# Headstage_Mainboard.net
KiCad netlist of a schematic drawn in Altium Designer
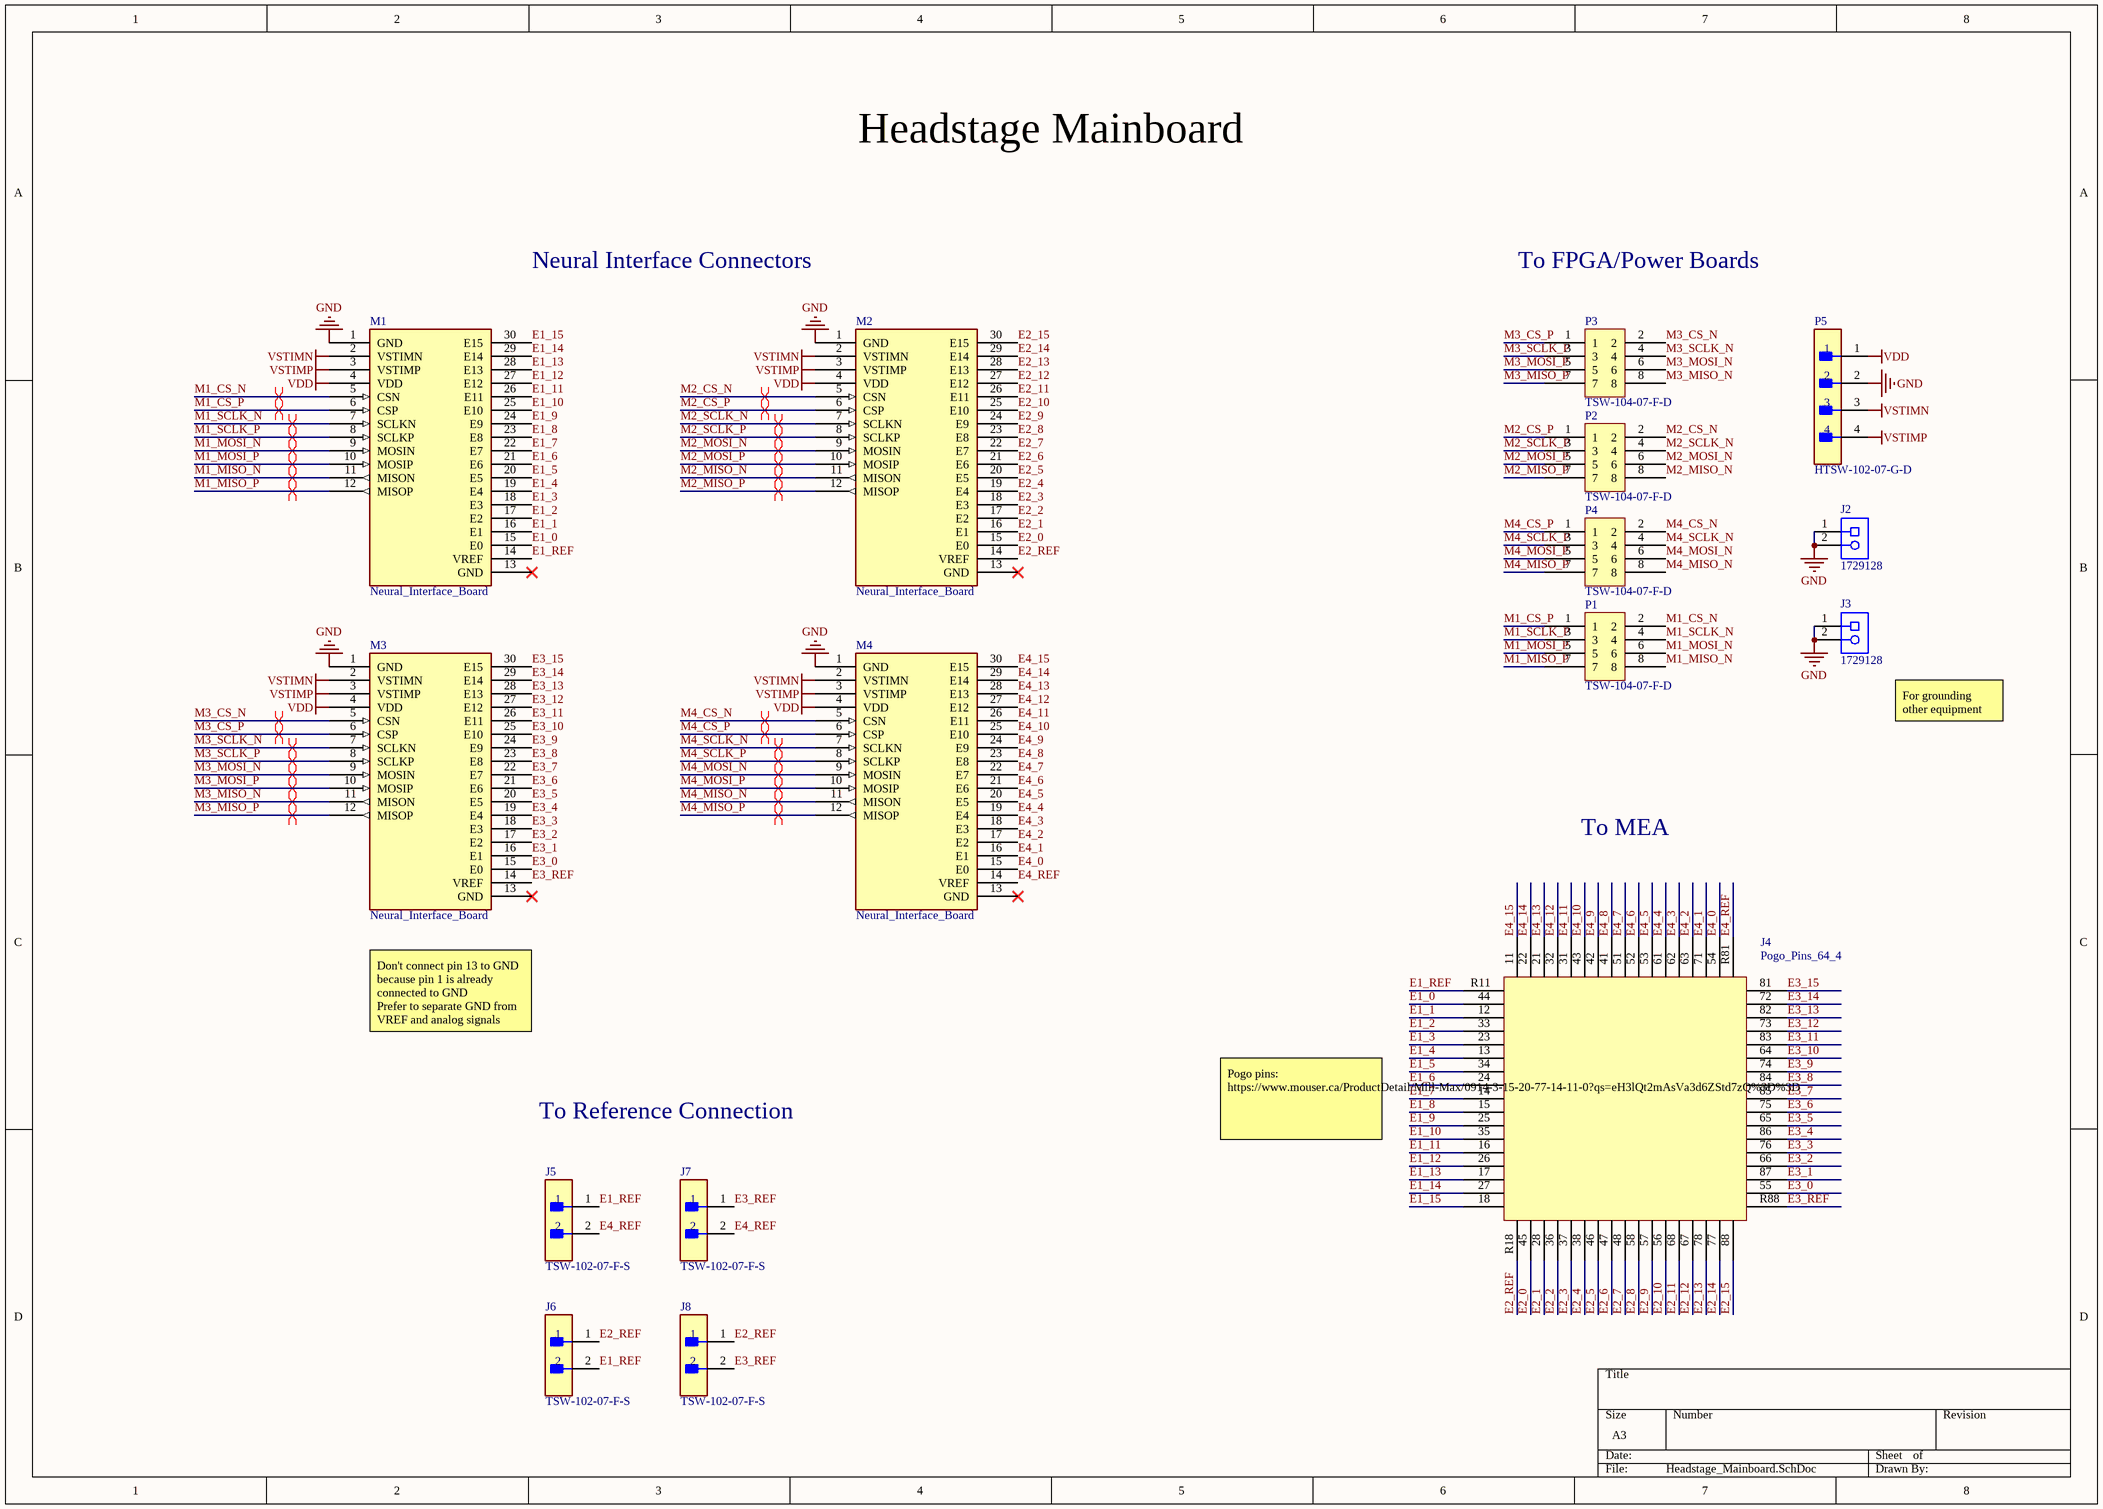
[diagram p0: Headstage_Mainboard.SchDoc]

(export (version "E")
  (design (tool "Eeschema 10.0.6"))
  (components
    (comp (ref "J2")
      (value "1729128")
      (footprint "PHOE-1729128-2_V")
      (description "PCB Terminal Block, 13.5 A, 400 V, 2-Pin THD, RoHS, Bulk")
      (fields (field (name "MANUFACTURER") "Phoenix Contact"))
      (libsource (lib "Altium Content Vault") (part "CN-2P-F-R2"))
    )
    (comp (ref "J3")
      (value "1729128")
      (footprint "PHOE-1729128-2_V")
      (description "PCB Terminal Block, 13.5 A, 400 V, 2-Pin THD, RoHS, Bulk")
      (fields (field (name "MANUFACTURER") "Phoenix Contact"))
      (libsource (lib "Altium Content Vault") (part "CN-2P-F-R2"))
    )
    (comp (ref "J4")
      (value "Pogo_Pins_64_4")
      (footprint "Pogo_Pins_64_4")
      (description "Pogo pins, 64 recording electrodes, 4 reference electrodes")
      (libsource (lib "OpenMEA") (part "Pogo_Pins_64_4"))
    )
    (comp (ref "J5")
      (value "TSW-102-07-F-S")
      (footprint "FP-TSW-102-07-F-S-MFG")
      (description "CONN HEADER VERT 2POS 2.54MM")
      (libsource (lib "Altium Content Vault") (part "3bc925449376181038e59eaffc5286c"))
    )
    (comp (ref "J6")
      (value "TSW-102-07-F-S")
      (footprint "FP-TSW-102-07-F-S-MFG")
      (description "CONN HEADER VERT 2POS 2.54MM")
      (libsource (lib "Altium Content Vault") (part "3bc925449376181038e59eaffc5286c"))
    )
    (comp (ref "J7")
      (value "TSW-102-07-F-S")
      (footprint "FP-TSW-102-07-F-S-MFG")
      (description "CONN HEADER VERT 2POS 2.54MM")
      (libsource (lib "Altium Content Vault") (part "3bc925449376181038e59eaffc5286c"))
    )
    (comp (ref "J8")
      (value "TSW-102-07-F-S")
      (footprint "FP-TSW-102-07-F-S-MFG")
      (description "CONN HEADER VERT 2POS 2.54MM")
      (libsource (lib "Altium Content Vault") (part "3bc925449376181038e59eaffc5286c"))
    )
    (comp (ref "M1")
      (value "Neural_Interface_Board")
      (footprint "Neural_Interface_Board")
      (libsource (lib "OpenMEA") (part "Neural_Interface_Board"))
    )
    (comp (ref "M2")
      (value "Neural_Interface_Board")
      (footprint "Neural_Interface_Board")
      (libsource (lib "OpenMEA") (part "Neural_Interface_Board"))
    )
    (comp (ref "M3")
      (value "Neural_Interface_Board")
      (footprint "Neural_Interface_Board")
      (libsource (lib "OpenMEA") (part "Neural_Interface_Board"))
    )
    (comp (ref "M4")
      (value "Neural_Interface_Board")
      (footprint "Neural_Interface_Board")
      (libsource (lib "OpenMEA") (part "Neural_Interface_Board"))
    )
    (comp (ref "P1")
      (value "TSW-104-07-F-D")
      (footprint "SAMTEC_TSW-104-07-F-D")
      (fields (field (name "MANUFACTURER") "Samtec"))
      (libsource (lib "LVDS") (part "TSW-104-07-F-D"))
    )
    (comp (ref "P2")
      (value "TSW-104-07-F-D")
      (footprint "SAMTEC_TSW-104-07-F-D")
      (fields (field (name "MANUFACTURER") "Samtec"))
      (libsource (lib "LVDS") (part "TSW-104-07-F-D"))
    )
    (comp (ref "P3")
      (value "TSW-104-07-F-D")
      (footprint "SAMTEC_TSW-104-07-F-D")
      (fields (field (name "MANUFACTURER") "Samtec"))
      (libsource (lib "LVDS") (part "TSW-104-07-F-D"))
    )
    (comp (ref "P4")
      (value "TSW-104-07-F-D")
      (footprint "SAMTEC_TSW-104-07-F-D")
      (fields (field (name "MANUFACTURER") "Samtec"))
      (libsource (lib "LVDS") (part "TSW-104-07-F-D"))
    )
    (comp (ref "P5")
      (value "HTSW-102-07-G-D")
      (footprint "FP-HTSW-102-07-G-D-MFG")
      (description "CONN HEADER VERT 4POS 2.54MM")
      (fields
        (field (name "MANUFACTURER") "Samtec")
        (field (name "OCTOPART") "https://octopart.com/htsw-102-07-g-d-samtec-10531767")
      )
      (libsource (lib "Altium Content Vault") (part "299a8cea1bdcbc3624fe62c390fa72c"))
    )
  )
  (nets
    (net (code "1") (name "/E1_0") (class "Default")
      (node (ref "J4") (pin "44") (pintype "passive"))
      (node (ref "M1") (pin "15") (pinfunction "E0_15") (pintype "passive"))
    )
    (net (code "2") (name "/E1_1") (class "Default")
      (node (ref "J4") (pin "12") (pintype "passive"))
      (node (ref "M1") (pin "16") (pinfunction "E1_16") (pintype "passive"))
    )
    (net (code "3") (name "/E1_2") (class "Default")
      (node (ref "J4") (pin "33") (pintype "passive"))
      (node (ref "M1") (pin "17") (pinfunction "E2_17") (pintype "passive"))
    )
    (net (code "4") (name "/E1_3") (class "Default")
      (node (ref "J4") (pin "23") (pintype "passive"))
      (node (ref "M1") (pin "18") (pinfunction "E3_18") (pintype "passive"))
    )
    (net (code "5") (name "/E1_4") (class "Default")
      (node (ref "J4") (pin "13") (pintype "passive"))
      (node (ref "M1") (pin "19") (pinfunction "E4_19") (pintype "passive"))
    )
    (net (code "6") (name "/E1_5") (class "Default")
      (node (ref "J4") (pin "34") (pintype "passive"))
      (node (ref "M1") (pin "20") (pinfunction "E5_20") (pintype "passive"))
    )
    (net (code "7") (name "/E1_6") (class "Default")
      (node (ref "J4") (pin "24") (pintype "passive"))
      (node (ref "M1") (pin "21") (pinfunction "E6_21") (pintype "passive"))
    )
    (net (code "8") (name "/E1_7") (class "Default")
      (node (ref "J4") (pin "14") (pintype "passive"))
      (node (ref "M1") (pin "22") (pinfunction "E7_22") (pintype "passive"))
    )
    (net (code "9") (name "/E1_8") (class "Default")
      (node (ref "J4") (pin "15") (pintype "passive"))
      (node (ref "M1") (pin "23") (pinfunction "E8_23") (pintype "passive"))
    )
    (net (code "10") (name "/E1_9") (class "Default")
      (node (ref "J4") (pin "25") (pintype "passive"))
      (node (ref "M1") (pin "24") (pinfunction "E9_24") (pintype "passive"))
    )
    (net (code "11") (name "/E1_10") (class "Default")
      (node (ref "J4") (pin "35") (pintype "passive"))
      (node (ref "M1") (pin "25") (pinfunction "E10_25") (pintype "passive"))
    )
    (net (code "12") (name "/E1_11") (class "Default")
      (node (ref "J4") (pin "16") (pintype "passive"))
      (node (ref "M1") (pin "26") (pinfunction "E11_26") (pintype "passive"))
    )
    (net (code "13") (name "/E1_12") (class "Default")
      (node (ref "J4") (pin "26") (pintype "passive"))
      (node (ref "M1") (pin "27") (pinfunction "E12_27") (pintype "passive"))
    )
    (net (code "14") (name "/E1_13") (class "Default")
      (node (ref "J4") (pin "17") (pintype "passive"))
      (node (ref "M1") (pin "28") (pinfunction "E13_28") (pintype "passive"))
    )
    (net (code "15") (name "/E1_14") (class "Default")
      (node (ref "J4") (pin "27") (pintype "passive"))
      (node (ref "M1") (pin "29") (pinfunction "E14_29") (pintype "passive"))
    )
    (net (code "16") (name "/E1_15") (class "Default")
      (node (ref "J4") (pin "18") (pintype "passive"))
      (node (ref "M1") (pin "30") (pinfunction "E15_30") (pintype "passive"))
    )
    (net (code "17") (name "/E1_REF") (class "Default")
      (node (ref "J4") (pin "R11") (pintype "passive"))
      (node (ref "J5") (pin "1") (pinfunction "1_1") (pintype "passive"))
      (node (ref "J6") (pin "2") (pinfunction "2_2") (pintype "passive"))
      (node (ref "M1") (pin "14") (pinfunction "VREF_14") (pintype "passive"))
    )
    (net (code "18") (name "/E2_0") (class "Default")
      (node (ref "J4") (pin "45") (pintype "passive"))
      (node (ref "M2") (pin "15") (pinfunction "E0_15") (pintype "passive"))
    )
    (net (code "19") (name "/E2_1") (class "Default")
      (node (ref "J4") (pin "28") (pintype "passive"))
      (node (ref "M2") (pin "16") (pinfunction "E1_16") (pintype "passive"))
    )
    (net (code "20") (name "/E2_2") (class "Default")
      (node (ref "J4") (pin "36") (pintype "passive"))
      (node (ref "M2") (pin "17") (pinfunction "E2_17") (pintype "passive"))
    )
    (net (code "21") (name "/E2_3") (class "Default")
      (node (ref "J4") (pin "37") (pintype "passive"))
      (node (ref "M2") (pin "18") (pinfunction "E3_18") (pintype "passive"))
    )
    (net (code "22") (name "/E2_4") (class "Default")
      (node (ref "J4") (pin "38") (pintype "passive"))
      (node (ref "M2") (pin "19") (pinfunction "E4_19") (pintype "passive"))
    )
    (net (code "23") (name "/E2_5") (class "Default")
      (node (ref "J4") (pin "46") (pintype "passive"))
      (node (ref "M2") (pin "20") (pinfunction "E5_20") (pintype "passive"))
    )
    (net (code "24") (name "/E2_6") (class "Default")
      (node (ref "J4") (pin "47") (pintype "passive"))
      (node (ref "M2") (pin "21") (pinfunction "E6_21") (pintype "passive"))
    )
    (net (code "25") (name "/E2_7") (class "Default")
      (node (ref "J4") (pin "48") (pintype "passive"))
      (node (ref "M2") (pin "22") (pinfunction "E7_22") (pintype "passive"))
    )
    (net (code "26") (name "/E2_8") (class "Default")
      (node (ref "J4") (pin "58") (pintype "passive"))
      (node (ref "M2") (pin "23") (pinfunction "E8_23") (pintype "passive"))
    )
    (net (code "27") (name "/E2_9") (class "Default")
      (node (ref "J4") (pin "57") (pintype "passive"))
      (node (ref "M2") (pin "24") (pinfunction "E9_24") (pintype "passive"))
    )
    (net (code "28") (name "/E2_10") (class "Default")
      (node (ref "J4") (pin "56") (pintype "passive"))
      (node (ref "M2") (pin "25") (pinfunction "E10_25") (pintype "passive"))
    )
    (net (code "29") (name "/E2_11") (class "Default")
      (node (ref "J4") (pin "68") (pintype "passive"))
      (node (ref "M2") (pin "26") (pinfunction "E11_26") (pintype "passive"))
    )
    (net (code "30") (name "/E2_12") (class "Default")
      (node (ref "J4") (pin "67") (pintype "passive"))
      (node (ref "M2") (pin "27") (pinfunction "E12_27") (pintype "passive"))
    )
    (net (code "31") (name "/E2_13") (class "Default")
      (node (ref "J4") (pin "78") (pintype "passive"))
      (node (ref "M2") (pin "28") (pinfunction "E13_28") (pintype "passive"))
    )
    (net (code "32") (name "/E2_14") (class "Default")
      (node (ref "J4") (pin "77") (pintype "passive"))
      (node (ref "M2") (pin "29") (pinfunction "E14_29") (pintype "passive"))
    )
    (net (code "33") (name "/E2_15") (class "Default")
      (node (ref "J4") (pin "88") (pintype "passive"))
      (node (ref "M2") (pin "30") (pinfunction "E15_30") (pintype "passive"))
    )
    (net (code "34") (name "/E2_REF") (class "Default")
      (node (ref "J4") (pin "R18") (pintype "passive"))
      (node (ref "J6") (pin "1") (pinfunction "1_1") (pintype "passive"))
      (node (ref "J8") (pin "1") (pinfunction "1_1") (pintype "passive"))
      (node (ref "M2") (pin "14") (pinfunction "VREF_14") (pintype "passive"))
    )
    (net (code "35") (name "/E3_0") (class "Default")
      (node (ref "J4") (pin "55") (pintype "passive"))
      (node (ref "M3") (pin "15") (pinfunction "E0_15") (pintype "passive"))
    )
    (net (code "36") (name "/E3_1") (class "Default")
      (node (ref "J4") (pin "87") (pintype "passive"))
      (node (ref "M3") (pin "16") (pinfunction "E1_16") (pintype "passive"))
    )
    (net (code "37") (name "/E3_2") (class "Default")
      (node (ref "J4") (pin "66") (pintype "passive"))
      (node (ref "M3") (pin "17") (pinfunction "E2_17") (pintype "passive"))
    )
    (net (code "38") (name "/E3_3") (class "Default")
      (node (ref "J4") (pin "76") (pintype "passive"))
      (node (ref "M3") (pin "18") (pinfunction "E3_18") (pintype "passive"))
    )
    (net (code "39") (name "/E3_4") (class "Default")
      (node (ref "J4") (pin "86") (pintype "passive"))
      (node (ref "M3") (pin "19") (pinfunction "E4_19") (pintype "passive"))
    )
    (net (code "40") (name "/E3_5") (class "Default")
      (node (ref "J4") (pin "65") (pintype "passive"))
      (node (ref "M3") (pin "20") (pinfunction "E5_20") (pintype "passive"))
    )
    (net (code "41") (name "/E3_6") (class "Default")
      (node (ref "J4") (pin "75") (pintype "passive"))
      (node (ref "M3") (pin "21") (pinfunction "E6_21") (pintype "passive"))
    )
    (net (code "42") (name "/E3_7") (class "Default")
      (node (ref "J4") (pin "85") (pintype "passive"))
      (node (ref "M3") (pin "22") (pinfunction "E7_22") (pintype "passive"))
    )
    (net (code "43") (name "/E3_8") (class "Default")
      (node (ref "J4") (pin "84") (pintype "passive"))
      (node (ref "M3") (pin "23") (pinfunction "E8_23") (pintype "passive"))
    )
    (net (code "44") (name "/E3_9") (class "Default")
      (node (ref "J4") (pin "74") (pintype "passive"))
      (node (ref "M3") (pin "24") (pinfunction "E9_24") (pintype "passive"))
    )
    (net (code "45") (name "/E3_10") (class "Default")
      (node (ref "J4") (pin "64") (pintype "passive"))
      (node (ref "M3") (pin "25") (pinfunction "E10_25") (pintype "passive"))
    )
    (net (code "46") (name "/E3_11") (class "Default")
      (node (ref "J4") (pin "83") (pintype "passive"))
      (node (ref "M3") (pin "26") (pinfunction "E11_26") (pintype "passive"))
    )
    (net (code "47") (name "/E3_12") (class "Default")
      (node (ref "J4") (pin "73") (pintype "passive"))
      (node (ref "M3") (pin "27") (pinfunction "E12_27") (pintype "passive"))
    )
    (net (code "48") (name "/E3_13") (class "Default")
      (node (ref "J4") (pin "82") (pintype "passive"))
      (node (ref "M3") (pin "28") (pinfunction "E13_28") (pintype "passive"))
    )
    (net (code "49") (name "/E3_14") (class "Default")
      (node (ref "J4") (pin "72") (pintype "passive"))
      (node (ref "M3") (pin "29") (pinfunction "E14_29") (pintype "passive"))
    )
    (net (code "50") (name "/E3_15") (class "Default")
      (node (ref "J4") (pin "81") (pintype "passive"))
      (node (ref "M3") (pin "30") (pinfunction "E15_30") (pintype "passive"))
    )
    (net (code "51") (name "/E3_REF") (class "Default")
      (node (ref "J4") (pin "R88") (pintype "passive"))
      (node (ref "J7") (pin "1") (pinfunction "1_1") (pintype "passive"))
      (node (ref "J8") (pin "2") (pinfunction "2_2") (pintype "passive"))
      (node (ref "M3") (pin "14") (pinfunction "VREF_14") (pintype "passive"))
    )
    (net (code "52") (name "/E4_0") (class "Default")
      (node (ref "J4") (pin "54") (pintype "passive"))
      (node (ref "M4") (pin "15") (pinfunction "E0_15") (pintype "passive"))
    )
    (net (code "53") (name "/E4_1") (class "Default")
      (node (ref "J4") (pin "71") (pintype "passive"))
      (node (ref "M4") (pin "16") (pinfunction "E1_16") (pintype "passive"))
    )
    (net (code "54") (name "/E4_2") (class "Default")
      (node (ref "J4") (pin "63") (pintype "passive"))
      (node (ref "M4") (pin "17") (pinfunction "E2_17") (pintype "passive"))
    )
    (net (code "55") (name "/E4_3") (class "Default")
      (node (ref "J4") (pin "62") (pintype "passive"))
      (node (ref "M4") (pin "18") (pinfunction "E3_18") (pintype "passive"))
    )
    (net (code "56") (name "/E4_4") (class "Default")
      (node (ref "J4") (pin "61") (pintype "passive"))
      (node (ref "M4") (pin "19") (pinfunction "E4_19") (pintype "passive"))
    )
    (net (code "57") (name "/E4_5") (class "Default")
      (node (ref "J4") (pin "53") (pintype "passive"))
      (node (ref "M4") (pin "20") (pinfunction "E5_20") (pintype "passive"))
    )
    (net (code "58") (name "/E4_6") (class "Default")
      (node (ref "J4") (pin "52") (pintype "passive"))
      (node (ref "M4") (pin "21") (pinfunction "E6_21") (pintype "passive"))
    )
    (net (code "59") (name "/E4_7") (class "Default")
      (node (ref "J4") (pin "51") (pintype "passive"))
      (node (ref "M4") (pin "22") (pinfunction "E7_22") (pintype "passive"))
    )
    (net (code "60") (name "/E4_8") (class "Default")
      (node (ref "J4") (pin "41") (pintype "passive"))
      (node (ref "M4") (pin "23") (pinfunction "E8_23") (pintype "passive"))
    )
    (net (code "61") (name "/E4_9") (class "Default")
      (node (ref "J4") (pin "42") (pintype "passive"))
      (node (ref "M4") (pin "24") (pinfunction "E9_24") (pintype "passive"))
    )
    (net (code "62") (name "/E4_10") (class "Default")
      (node (ref "J4") (pin "43") (pintype "passive"))
      (node (ref "M4") (pin "25") (pinfunction "E10_25") (pintype "passive"))
    )
    (net (code "63") (name "/E4_11") (class "Default")
      (node (ref "J4") (pin "31") (pintype "passive"))
      (node (ref "M4") (pin "26") (pinfunction "E11_26") (pintype "passive"))
    )
    (net (code "64") (name "/E4_12") (class "Default")
      (node (ref "J4") (pin "32") (pintype "passive"))
      (node (ref "M4") (pin "27") (pinfunction "E12_27") (pintype "passive"))
    )
    (net (code "65") (name "/E4_13") (class "Default")
      (node (ref "J4") (pin "21") (pintype "passive"))
      (node (ref "M4") (pin "28") (pinfunction "E13_28") (pintype "passive"))
    )
    (net (code "66") (name "/E4_14") (class "Default")
      (node (ref "J4") (pin "22") (pintype "passive"))
      (node (ref "M4") (pin "29") (pinfunction "E14_29") (pintype "passive"))
    )
    (net (code "67") (name "/E4_15") (class "Default")
      (node (ref "J4") (pin "11") (pintype "passive"))
      (node (ref "M4") (pin "30") (pinfunction "E15_30") (pintype "passive"))
    )
    (net (code "68") (name "/E4_REF") (class "Default")
      (node (ref "J4") (pin "R81") (pintype "passive"))
      (node (ref "J5") (pin "2") (pinfunction "2_2") (pintype "passive"))
      (node (ref "J7") (pin "2") (pinfunction "2_2") (pintype "passive"))
      (node (ref "M4") (pin "14") (pinfunction "VREF_14") (pintype "passive"))
    )
    (net (code "69") (name "/M1_CS_N") (class "Default")
      (node (ref "M1") (pin "5") (pinfunction "CSN_5") (pintype "input"))
      (node (ref "P1") (pin "2") (pinfunction "2_2") (pintype "passive"))
    )
    (net (code "70") (name "/M1_CS_P") (class "Default")
      (node (ref "M1") (pin "6") (pinfunction "CSP_6") (pintype "input"))
      (node (ref "P1") (pin "1") (pinfunction "1_1") (pintype "passive"))
    )
    (net (code "71") (name "/M1_MISO_N") (class "Default")
      (node (ref "M1") (pin "11") (pinfunction "MISON_11") (pintype "output"))
      (node (ref "P1") (pin "8") (pinfunction "8_8") (pintype "passive"))
    )
    (net (code "72") (name "/M1_MISO_P") (class "Default")
      (node (ref "M1") (pin "12") (pinfunction "MISOP_12") (pintype "output"))
      (node (ref "P1") (pin "7") (pinfunction "7_7") (pintype "passive"))
    )
    (net (code "73") (name "/M1_MOSI_N") (class "Default")
      (node (ref "M1") (pin "9") (pinfunction "MOSIN_9") (pintype "input"))
      (node (ref "P1") (pin "6") (pinfunction "6_6") (pintype "passive"))
    )
    (net (code "74") (name "/M1_MOSI_P") (class "Default")
      (node (ref "M1") (pin "10") (pinfunction "MOSIP_10") (pintype "input"))
      (node (ref "P1") (pin "5") (pinfunction "5_5") (pintype "passive"))
    )
    (net (code "75") (name "/M1_SCLK_N") (class "Default")
      (node (ref "M1") (pin "7") (pinfunction "SCLKN_7") (pintype "input"))
      (node (ref "P1") (pin "4") (pinfunction "4_4") (pintype "passive"))
    )
    (net (code "76") (name "/M1_SCLK_P") (class "Default")
      (node (ref "M1") (pin "8") (pinfunction "SCLKP_8") (pintype "input"))
      (node (ref "P1") (pin "3") (pinfunction "3_3") (pintype "passive"))
    )
    (net (code "77") (name "/M2_CS_N") (class "Default")
      (node (ref "M2") (pin "5") (pinfunction "CSN_5") (pintype "input"))
      (node (ref "P2") (pin "2") (pinfunction "2_2") (pintype "passive"))
    )
    (net (code "78") (name "/M2_CS_P") (class "Default")
      (node (ref "M2") (pin "6") (pinfunction "CSP_6") (pintype "input"))
      (node (ref "P2") (pin "1") (pinfunction "1_1") (pintype "passive"))
    )
    (net (code "79") (name "/M2_MISO_N") (class "Default")
      (node (ref "M2") (pin "11") (pinfunction "MISON_11") (pintype "output"))
      (node (ref "P2") (pin "8") (pinfunction "8_8") (pintype "passive"))
    )
    (net (code "80") (name "/M2_MISO_P") (class "Default")
      (node (ref "M2") (pin "12") (pinfunction "MISOP_12") (pintype "output"))
      (node (ref "P2") (pin "7") (pinfunction "7_7") (pintype "passive"))
    )
    (net (code "81") (name "/M2_MOSI_N") (class "Default")
      (node (ref "M2") (pin "9") (pinfunction "MOSIN_9") (pintype "input"))
      (node (ref "P2") (pin "6") (pinfunction "6_6") (pintype "passive"))
    )
    (net (code "82") (name "/M2_MOSI_P") (class "Default")
      (node (ref "M2") (pin "10") (pinfunction "MOSIP_10") (pintype "input"))
      (node (ref "P2") (pin "5") (pinfunction "5_5") (pintype "passive"))
    )
    (net (code "83") (name "/M2_SCLK_N") (class "Default")
      (node (ref "M2") (pin "7") (pinfunction "SCLKN_7") (pintype "input"))
      (node (ref "P2") (pin "4") (pinfunction "4_4") (pintype "passive"))
    )
    (net (code "84") (name "/M2_SCLK_P") (class "Default")
      (node (ref "M2") (pin "8") (pinfunction "SCLKP_8") (pintype "input"))
      (node (ref "P2") (pin "3") (pinfunction "3_3") (pintype "passive"))
    )
    (net (code "85") (name "/M3_CS_N") (class "Default")
      (node (ref "M3") (pin "5") (pinfunction "CSN_5") (pintype "input"))
      (node (ref "P3") (pin "2") (pinfunction "2_2") (pintype "passive"))
    )
    (net (code "86") (name "/M3_CS_P") (class "Default")
      (node (ref "M3") (pin "6") (pinfunction "CSP_6") (pintype "input"))
      (node (ref "P3") (pin "1") (pinfunction "1_1") (pintype "passive"))
    )
    (net (code "87") (name "/M3_MISO_N") (class "Default")
      (node (ref "M3") (pin "11") (pinfunction "MISON_11") (pintype "output"))
      (node (ref "P3") (pin "8") (pinfunction "8_8") (pintype "passive"))
    )
    (net (code "88") (name "/M3_MISO_P") (class "Default")
      (node (ref "M3") (pin "12") (pinfunction "MISOP_12") (pintype "output"))
      (node (ref "P3") (pin "7") (pinfunction "7_7") (pintype "passive"))
    )
    (net (code "89") (name "/M3_MOSI_N") (class "Default")
      (node (ref "M3") (pin "9") (pinfunction "MOSIN_9") (pintype "input"))
      (node (ref "P3") (pin "6") (pinfunction "6_6") (pintype "passive"))
    )
    (net (code "90") (name "/M3_MOSI_P") (class "Default")
      (node (ref "M3") (pin "10") (pinfunction "MOSIP_10") (pintype "input"))
      (node (ref "P3") (pin "5") (pinfunction "5_5") (pintype "passive"))
    )
    (net (code "91") (name "/M3_SCLK_N") (class "Default")
      (node (ref "M3") (pin "7") (pinfunction "SCLKN_7") (pintype "input"))
      (node (ref "P3") (pin "4") (pinfunction "4_4") (pintype "passive"))
    )
    (net (code "92") (name "/M3_SCLK_P") (class "Default")
      (node (ref "M3") (pin "8") (pinfunction "SCLKP_8") (pintype "input"))
      (node (ref "P3") (pin "3") (pinfunction "3_3") (pintype "passive"))
    )
    (net (code "93") (name "/M4_CS_N") (class "Default")
      (node (ref "M4") (pin "5") (pinfunction "CSN_5") (pintype "input"))
      (node (ref "P4") (pin "2") (pinfunction "2_2") (pintype "passive"))
    )
    (net (code "94") (name "/M4_CS_P") (class "Default")
      (node (ref "M4") (pin "6") (pinfunction "CSP_6") (pintype "input"))
      (node (ref "P4") (pin "1") (pinfunction "1_1") (pintype "passive"))
    )
    (net (code "95") (name "/M4_MISO_N") (class "Default")
      (node (ref "M4") (pin "11") (pinfunction "MISON_11") (pintype "output"))
      (node (ref "P4") (pin "8") (pinfunction "8_8") (pintype "passive"))
    )
    (net (code "96") (name "/M4_MISO_P") (class "Default")
      (node (ref "M4") (pin "12") (pinfunction "MISOP_12") (pintype "output"))
      (node (ref "P4") (pin "7") (pinfunction "7_7") (pintype "passive"))
    )
    (net (code "97") (name "/M4_MOSI_N") (class "Default")
      (node (ref "M4") (pin "9") (pinfunction "MOSIN_9") (pintype "input"))
      (node (ref "P4") (pin "6") (pinfunction "6_6") (pintype "passive"))
    )
    (net (code "98") (name "/M4_MOSI_P") (class "Default")
      (node (ref "M4") (pin "10") (pinfunction "MOSIP_10") (pintype "input"))
      (node (ref "P4") (pin "5") (pinfunction "5_5") (pintype "passive"))
    )
    (net (code "99") (name "/M4_SCLK_N") (class "Default")
      (node (ref "M4") (pin "7") (pinfunction "SCLKN_7") (pintype "input"))
      (node (ref "P4") (pin "4") (pinfunction "4_4") (pintype "passive"))
    )
    (net (code "100") (name "/M4_SCLK_P") (class "Default")
      (node (ref "M4") (pin "8") (pinfunction "SCLKP_8") (pintype "input"))
      (node (ref "P4") (pin "3") (pinfunction "3_3") (pintype "passive"))
    )
    (net (code "101") (name "GND") (class "Default")
      (node (ref "J2") (pin "1") (pinfunction "1_1") (pintype "passive"))
      (node (ref "J2") (pin "2") (pinfunction "2_2") (pintype "passive"))
      (node (ref "J3") (pin "1") (pinfunction "1_1") (pintype "passive"))
      (node (ref "J3") (pin "2") (pinfunction "2_2") (pintype "passive"))
      (node (ref "M1") (pin "1") (pinfunction "GND_1") (pintype "power_in"))
      (node (ref "M2") (pin "1") (pinfunction "GND_1") (pintype "power_in"))
      (node (ref "M3") (pin "1") (pinfunction "GND_1") (pintype "power_in"))
      (node (ref "M4") (pin "1") (pinfunction "GND_1") (pintype "power_in"))
      (node (ref "P5") (pin "2") (pinfunction "2_2") (pintype "passive"))
    )
    (net (code "102") (name "VDD") (class "Default")
      (node (ref "M1") (pin "4") (pinfunction "VDD_4") (pintype "power_in"))
      (node (ref "M2") (pin "4") (pinfunction "VDD_4") (pintype "power_in"))
      (node (ref "M3") (pin "4") (pinfunction "VDD_4") (pintype "power_in"))
      (node (ref "M4") (pin "4") (pinfunction "VDD_4") (pintype "power_in"))
      (node (ref "P5") (pin "1") (pinfunction "1_1") (pintype "passive"))
    )
    (net (code "103") (name "VSTIMN") (class "Default")
      (node (ref "M1") (pin "2") (pinfunction "VSTIMN_2") (pintype "power_in"))
      (node (ref "M2") (pin "2") (pinfunction "VSTIMN_2") (pintype "power_in"))
      (node (ref "M3") (pin "2") (pinfunction "VSTIMN_2") (pintype "power_in"))
      (node (ref "M4") (pin "2") (pinfunction "VSTIMN_2") (pintype "power_in"))
      (node (ref "P5") (pin "3") (pinfunction "3_3") (pintype "passive"))
    )
    (net (code "104") (name "VSTIMP") (class "Default")
      (node (ref "M1") (pin "3") (pinfunction "VSTIMP_3") (pintype "power_in"))
      (node (ref "M2") (pin "3") (pinfunction "VSTIMP_3") (pintype "power_in"))
      (node (ref "M3") (pin "3") (pinfunction "VSTIMP_3") (pintype "power_in"))
      (node (ref "M4") (pin "3") (pinfunction "VSTIMP_3") (pintype "power_in"))
      (node (ref "P5") (pin "4") (pinfunction "4_4") (pintype "passive"))
    )
    (net (code "105") (name "unconnected-(M1-GND-Pad13)") (class "Default")
      (node (ref "M1") (pin "13") (pinfunction "GND_13") (pintype "power_in+no_connect"))
    )
    (net (code "106") (name "unconnected-(M2-GND-Pad13)") (class "Default")
      (node (ref "M2") (pin "13") (pinfunction "GND_13") (pintype "power_in+no_connect"))
    )
    (net (code "107") (name "unconnected-(M3-GND-Pad13)") (class "Default")
      (node (ref "M3") (pin "13") (pinfunction "GND_13") (pintype "power_in+no_connect"))
    )
    (net (code "108") (name "unconnected-(M4-GND-Pad13)") (class "Default")
      (node (ref "M4") (pin "13") (pinfunction "GND_13") (pintype "power_in+no_connect"))
    )
  )
)
